# PWM_Output.net
KiCad netlist of a schematic drawn in Altium Designer
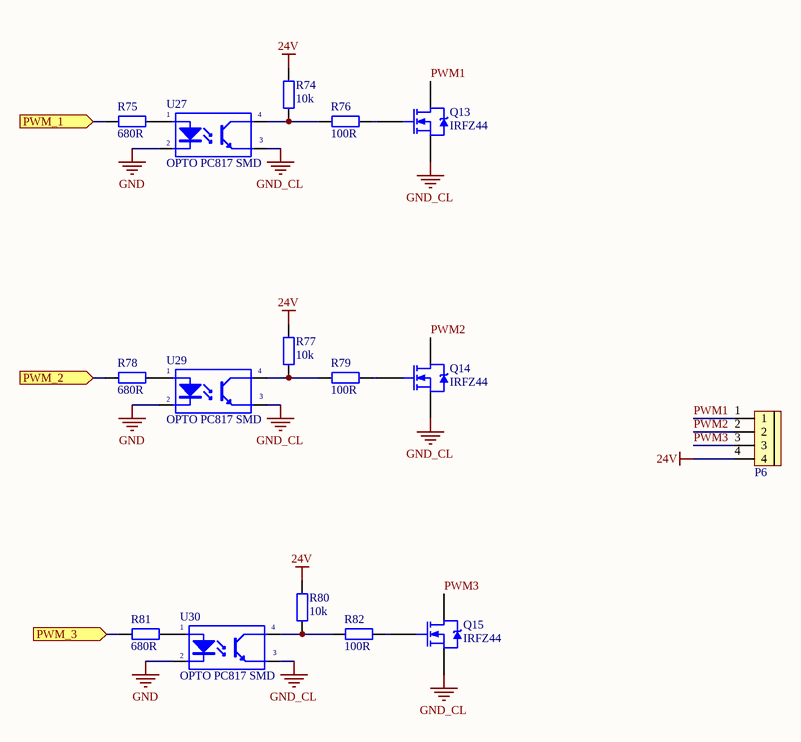
[diagram p0: PWM_Output.SchDoc]

(export (version "E")
  (design (tool "Eeschema 10.0.6"))
  (components
    (comp (ref "P6")
      (value "CON 4 EDG5.08")
      (footprint "CON 4 4EDG5.08")
      (description "Cắm")
      (libsource (lib "Altium_Lib_by_KhueNguyenCreator") (part "CON 4 EDG5.08"))
    )
    (comp (ref "Q13")
      (value "IRFZ44")
      (footprint "TO220")
      (description "N-Channel Power MOSFET")
      (libsource (lib "Altium_Lib_by_KhueNguyenCreator") (part "IRFZ44 DIP"))
    )
    (comp (ref "Q14")
      (value "IRFZ44")
      (footprint "TO220")
      (description "N-Channel Power MOSFET")
      (libsource (lib "Altium_Lib_by_KhueNguyenCreator") (part "IRFZ44 DIP"))
    )
    (comp (ref "Q15")
      (value "IRFZ44")
      (footprint "TO220")
      (description "N-Channel Power MOSFET")
      (libsource (lib "Altium_Lib_by_KhueNguyenCreator") (part "IRFZ44 DIP"))
    )
    (comp (ref "R74")
      (value "10k")
      (footprint "tro smd 0805")
      (description "Dán")
      (libsource (lib "Altium_Lib_by_KhueNguyenCreator") (part "Tro 0805 1% 10k"))
    )
    (comp (ref "R75")
      (value "680R")
      (footprint "tro smd 0805")
      (description "Dán")
      (libsource (lib "Altium_Lib_by_KhueNguyenCreator") (part "Tro 0805 1% 680R"))
    )
    (comp (ref "R76")
      (value "100R")
      (footprint "tro smd 0805")
      (description "Dán")
      (libsource (lib "Altium_Lib_by_KhueNguyenCreator") (part "Tro 0805 5% 100R"))
    )
    (comp (ref "R77")
      (value "10k")
      (footprint "tro smd 0805")
      (description "Dán")
      (libsource (lib "Altium_Lib_by_KhueNguyenCreator") (part "Tro 0805 1% 10k"))
    )
    (comp (ref "R78")
      (value "680R")
      (footprint "tro smd 0805")
      (description "Dán")
      (libsource (lib "Altium_Lib_by_KhueNguyenCreator") (part "Tro 0805 1% 680R"))
    )
    (comp (ref "R79")
      (value "100R")
      (footprint "tro smd 0805")
      (description "Dán")
      (libsource (lib "Altium_Lib_by_KhueNguyenCreator") (part "Tro 0805 5% 100R"))
    )
    (comp (ref "R80")
      (value "10k")
      (footprint "tro smd 0805")
      (description "Dán")
      (libsource (lib "Altium_Lib_by_KhueNguyenCreator") (part "Tro 0805 1% 10k"))
    )
    (comp (ref "R81")
      (value "680R")
      (footprint "tro smd 0805")
      (description "Dán")
      (libsource (lib "Altium_Lib_by_KhueNguyenCreator") (part "Tro 0805 1% 680R"))
    )
    (comp (ref "R82")
      (value "100R")
      (footprint "tro smd 0805")
      (description "Dán")
      (libsource (lib "Altium_Lib_by_KhueNguyenCreator") (part "Tro 0805 5% 100R"))
    )
    (comp (ref "U27")
      (value "OPTO PC817 SMD")
      (footprint "SOP4")
      (description "Single Opto")
      (libsource (lib "Altium_Lib_by_KhueNguyenCreator") (part "OPTO PC817 SMD"))
    )
    (comp (ref "U29")
      (value "OPTO PC817 SMD")
      (footprint "SOP4")
      (description "Single Opto")
      (libsource (lib "Altium_Lib_by_KhueNguyenCreator") (part "OPTO PC817 SMD"))
    )
    (comp (ref "U30")
      (value "OPTO PC817 SMD")
      (footprint "SOP4")
      (description "Single Opto")
      (libsource (lib "Altium_Lib_by_KhueNguyenCreator") (part "OPTO PC817 SMD"))
    )
  )
  (nets
    (net (code "1") (name "/PWM1") (class "Default")
      (node (ref "P6") (pin "1") (pinfunction "1_1") (pintype "passive"))
      (node (ref "Q13") (pin "2") (pinfunction "D_2") (pintype "passive"))
    )
    (net (code "2") (name "/PWM2") (class "Default")
      (node (ref "P6") (pin "2") (pinfunction "2_2") (pintype "passive"))
      (node (ref "Q14") (pin "2") (pinfunction "D_2") (pintype "passive"))
    )
    (net (code "3") (name "/PWM3") (class "Default")
      (node (ref "P6") (pin "3") (pinfunction "3_3") (pintype "passive"))
      (node (ref "Q15") (pin "2") (pinfunction "D_2") (pintype "passive"))
    )
    (net (code "4") (name "/PWM_1") (class "Default")
      (node (ref "R75") (pin "1") (pinfunction "1_1") (pintype "passive"))
    )
    (net (code "5") (name "/PWM_2") (class "Default")
      (node (ref "R78") (pin "1") (pinfunction "1_1") (pintype "passive"))
    )
    (net (code "6") (name "/PWM_3") (class "Default")
      (node (ref "R81") (pin "1") (pinfunction "1_1") (pintype "passive"))
    )
    (net (code "7") (name "24V") (class "Default")
      (node (ref "P6") (pin "4") (pinfunction "4_4") (pintype "passive"))
      (node (ref "R74") (pin "1") (pinfunction "1_1") (pintype "passive"))
      (node (ref "R77") (pin "1") (pinfunction "1_1") (pintype "passive"))
      (node (ref "R80") (pin "1") (pinfunction "1_1") (pintype "passive"))
    )
    (net (code "8") (name "GND") (class "Default")
      (node (ref "U27") (pin "2") (pinfunction "K_2") (pintype "passive"))
      (node (ref "U29") (pin "2") (pinfunction "K_2") (pintype "passive"))
      (node (ref "U30") (pin "2") (pinfunction "K_2") (pintype "passive"))
    )
    (net (code "9") (name "GND_CL") (class "Default")
      (node (ref "Q13") (pin "3") (pinfunction "S_3") (pintype "passive"))
      (node (ref "Q14") (pin "3") (pinfunction "S_3") (pintype "passive"))
      (node (ref "Q15") (pin "3") (pinfunction "S_3") (pintype "passive"))
      (node (ref "U27") (pin "3") (pinfunction "E_3") (pintype "passive"))
      (node (ref "U29") (pin "3") (pinfunction "E_3") (pintype "passive"))
      (node (ref "U30") (pin "3") (pinfunction "E_3") (pintype "passive"))
    )
    (net (code "10") (name "Net-(Q13-G)") (class "Default")
      (node (ref "Q13") (pin "1") (pinfunction "G_1") (pintype "passive"))
      (node (ref "R76") (pin "2") (pinfunction "2_2") (pintype "passive"))
    )
    (net (code "11") (name "Net-(Q14-G)") (class "Default")
      (node (ref "Q14") (pin "1") (pinfunction "G_1") (pintype "passive"))
      (node (ref "R79") (pin "2") (pinfunction "2_2") (pintype "passive"))
    )
    (net (code "12") (name "Net-(Q15-G)") (class "Default")
      (node (ref "Q15") (pin "1") (pinfunction "G_1") (pintype "passive"))
      (node (ref "R82") (pin "2") (pinfunction "2_2") (pintype "passive"))
    )
    (net (code "13") (name "Net-(U27-A)") (class "Default")
      (node (ref "R75") (pin "2") (pinfunction "2_2") (pintype "passive"))
      (node (ref "U27") (pin "1") (pinfunction "A_1") (pintype "passive"))
    )
    (net (code "14") (name "Net-(U27-C)") (class "Default")
      (node (ref "R74") (pin "2") (pinfunction "2_2") (pintype "passive"))
      (node (ref "R76") (pin "1") (pinfunction "1_1") (pintype "passive"))
      (node (ref "U27") (pin "4") (pinfunction "C_4") (pintype "passive"))
    )
    (net (code "15") (name "Net-(U29-A)") (class "Default")
      (node (ref "R78") (pin "2") (pinfunction "2_2") (pintype "passive"))
      (node (ref "U29") (pin "1") (pinfunction "A_1") (pintype "passive"))
    )
    (net (code "16") (name "Net-(U29-C)") (class "Default")
      (node (ref "R77") (pin "2") (pinfunction "2_2") (pintype "passive"))
      (node (ref "R79") (pin "1") (pinfunction "1_1") (pintype "passive"))
      (node (ref "U29") (pin "4") (pinfunction "C_4") (pintype "passive"))
    )
    (net (code "17") (name "Net-(U30-A)") (class "Default")
      (node (ref "R81") (pin "2") (pinfunction "2_2") (pintype "passive"))
      (node (ref "U30") (pin "1") (pinfunction "A_1") (pintype "passive"))
    )
    (net (code "18") (name "Net-(U30-C)") (class "Default")
      (node (ref "R80") (pin "2") (pinfunction "2_2") (pintype "passive"))
      (node (ref "R82") (pin "1") (pinfunction "1_1") (pintype "passive"))
      (node (ref "U30") (pin "4") (pinfunction "C_4") (pintype "passive"))
    )
  )
)
